# enet_phy.net
KiCad netlist of a schematic drawn in Altium Designer
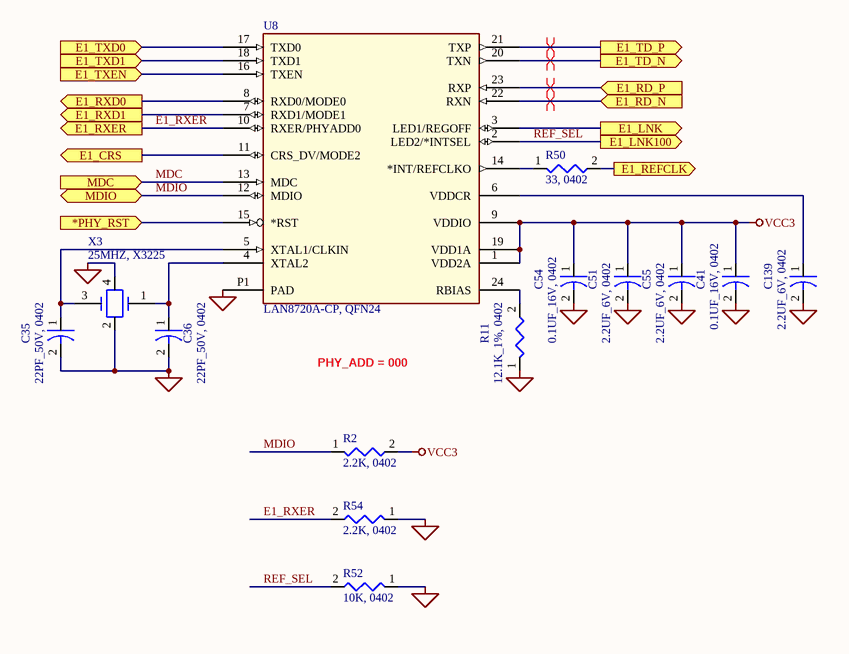
[diagram p0: enet_phy.SchDoc]

(export (version "E")
  (design (tool "Eeschema 10.0.6"))
  (components
    (comp (ref "C35")
      (value "22PF_50V, 0402")
      (footprint "0402C")
      (description "CAP - 0402 PKG")
      (libsource (lib "COGENT_Library") (part "22PF_50V, 0402"))
    )
    (comp (ref "C36")
      (value "22PF_50V, 0402")
      (footprint "0402C")
      (description "CAP - 0402 PKG")
      (libsource (lib "COGENT_Library") (part "22PF_50V, 0402"))
    )
    (comp (ref "C41")
      (value "0.1UF_16V, 0402")
      (footprint "0402C")
      (description "CAP - 0402 PKG")
      (libsource (lib "COGENT_Library") (part "0.1UF_16V, 0402"))
    )
    (comp (ref "C51")
      (value "2.2UF_6V, 0402")
      (footprint "0402C")
      (description "CAP - 0402 PKG")
      (libsource (lib "COGENT_Library") (part "2.2UF_6V, 0402"))
    )
    (comp (ref "C54")
      (value "0.1UF_16V, 0402")
      (footprint "0402C")
      (description "CAP - 0402 PKG")
      (libsource (lib "COGENT_Library") (part "0.1UF_16V, 0402"))
    )
    (comp (ref "C55")
      (value "2.2UF_6V, 0402")
      (footprint "0402C")
      (description "CAP - 0402 PKG")
      (libsource (lib "COGENT_Library") (part "2.2UF_6V, 0402"))
    )
    (comp (ref "C139")
      (value "2.2UF_6V, 0402")
      (footprint "0402C")
      (description "CAP - 0402 PKG")
      (libsource (lib "COGENT_Library") (part "2.2UF_6V, 0402"))
    )
    (comp (ref "R2")
      (value "2.2K, 0402")
      (footprint "0402R")
      (description "RES - 0402 PKG")
      (libsource (lib "COGENT_Library") (part "2.2K, 0402"))
    )
    (comp (ref "R11")
      (value "12.1K_1%, 0402")
      (footprint "0402R")
      (description "RES - 0402 PKG")
      (libsource (lib "COGENT_Library") (part "12.1K_1%, 0402"))
    )
    (comp (ref "R50")
      (value "33, 0402")
      (footprint "0402R")
      (description "RES - 0402 PKG")
      (libsource (lib "COGENT_Library") (part "33, 0402"))
    )
    (comp (ref "R52")
      (value "10K, 0402")
      (footprint "0402R")
      (description "RES - 0402 PKG")
      (libsource (lib "COGENT_Library") (part "10K, 0402"))
    )
    (comp (ref "R54")
      (value "2.2K, 0402")
      (footprint "0402R")
      (description "RES - 0402 PKG")
      (libsource (lib "COGENT_Library") (part "2.2K, 0402"))
    )
    (comp (ref "U8")
      (value "LAN8720A-CP, QFN24")
      (footprint "QFN24")
      (description "PHY - 10/100 RMII")
      (libsource (lib "COGENT_Library") (part "LAN8720A-CP, QFN24"))
    )
    (comp (ref "X3")
      (value "25MHZ, X3225")
      (footprint "X3225")
      (description "CRYSTAL - SMT, 3.2MM x 2.5MM, ABM8 PKG")
      (libsource (lib "COGENT_Library") (part "25MHZ, X3225"))
    )
  )
  (nets
    (net (code "1") (name "/*PHY_RST") (class "Default")
      (node (ref "U8") (pin "15") (pinfunction "*RST_15") (pintype "input"))
    )
    (net (code "2") (name "/E1_CRS") (class "Default")
      (node (ref "U8") (pin "11") (pinfunction "CRS_DV/MODE2_11") (pintype "bidirectional"))
    )
    (net (code "3") (name "/E1_LNK") (class "Default")
      (node (ref "U8") (pin "3") (pinfunction "LED1/REGOFF_3") (pintype "bidirectional"))
    )
    (net (code "4") (name "/E1_RD_N") (class "Default")
      (node (ref "U8") (pin "22") (pinfunction "RXN_22") (pintype "input"))
    )
    (net (code "5") (name "/E1_RD_P") (class "Default")
      (node (ref "U8") (pin "23") (pinfunction "RXP_23") (pintype "input"))
    )
    (net (code "6") (name "/E1_REFCLK") (class "Default")
      (node (ref "R50") (pin "2") (pinfunction "2_2") (pintype "passive"))
    )
    (net (code "7") (name "/E1_RXD0") (class "Default")
      (node (ref "U8") (pin "8") (pinfunction "RXD0/MODE0_8") (pintype "bidirectional"))
    )
    (net (code "8") (name "/E1_RXD1") (class "Default")
      (node (ref "U8") (pin "7") (pinfunction "RXD1/MODE1_7") (pintype "bidirectional"))
    )
    (net (code "9") (name "/E1_RXER") (class "Default")
      (node (ref "R54") (pin "2") (pinfunction "2_2") (pintype "passive"))
      (node (ref "U8") (pin "10") (pinfunction "RXER/PHYADD0_10") (pintype "bidirectional"))
    )
    (net (code "10") (name "/E1_TD_N") (class "Default")
      (node (ref "U8") (pin "20") (pinfunction "TXN_20") (pintype "output"))
    )
    (net (code "11") (name "/E1_TD_P") (class "Default")
      (node (ref "U8") (pin "21") (pinfunction "TXP_21") (pintype "output"))
    )
    (net (code "12") (name "/E1_TXD0") (class "Default")
      (node (ref "U8") (pin "17") (pinfunction "TXD0_17") (pintype "input"))
    )
    (net (code "13") (name "/E1_TXD1") (class "Default")
      (node (ref "U8") (pin "18") (pinfunction "TXD1_18") (pintype "input"))
    )
    (net (code "14") (name "/E1_TXEN") (class "Default")
      (node (ref "U8") (pin "16") (pinfunction "TXEN_16") (pintype "input"))
    )
    (net (code "15") (name "/MDC") (class "Default")
      (node (ref "U8") (pin "13") (pinfunction "MDC_13") (pintype "input"))
    )
    (net (code "16") (name "/MDIO") (class "Default")
      (node (ref "R2") (pin "1") (pinfunction "1_1") (pintype "passive"))
      (node (ref "U8") (pin "12") (pinfunction "MDIO_12") (pintype "bidirectional"))
    )
    (net (code "17") (name "/REF_SEL") (class "Default")
      (node (ref "R52") (pin "2") (pinfunction "2_2") (pintype "passive"))
      (node (ref "U8") (pin "2") (pinfunction "LED2/*INTSEL_2") (pintype "bidirectional"))
    )
    (net (code "18") (name "GND") (class "Default")
      (node (ref "C139") (pin "2") (pinfunction "2_2") (pintype "passive"))
      (node (ref "C35") (pin "2") (pinfunction "2_2") (pintype "passive"))
      (node (ref "C36") (pin "2") (pinfunction "2_2") (pintype "passive"))
      (node (ref "C41") (pin "2") (pinfunction "2_2") (pintype "passive"))
      (node (ref "C51") (pin "2") (pinfunction "2_2") (pintype "passive"))
      (node (ref "C54") (pin "2") (pinfunction "2_2") (pintype "passive"))
      (node (ref "C55") (pin "2") (pinfunction "2_2") (pintype "passive"))
      (node (ref "R11") (pin "1") (pinfunction "1_1") (pintype "passive"))
      (node (ref "R52") (pin "1") (pinfunction "1_1") (pintype "passive"))
      (node (ref "R54") (pin "1") (pinfunction "1_1") (pintype "passive"))
      (node (ref "U8") (pin "P1") (pinfunction "PAD_P1") (pintype "power_in"))
      (node (ref "X3") (pin "2") (pinfunction "2_2") (pintype "passive"))
      (node (ref "X3") (pin "4") (pinfunction "4_4") (pintype "passive"))
    )
    (net (code "19") (name "Net-(U8-*INT{slash}REFCLKO)") (class "Default")
      (node (ref "R50") (pin "1") (pinfunction "1_1") (pintype "passive"))
      (node (ref "U8") (pin "14") (pinfunction "*INT/REFCLKO_14") (pintype "output"))
    )
    (net (code "20") (name "Net-(U8-RBIAS)") (class "Default")
      (node (ref "R11") (pin "2") (pinfunction "2_2") (pintype "passive"))
      (node (ref "U8") (pin "24") (pinfunction "RBIAS_24") (pintype "passive"))
    )
    (net (code "21") (name "Net-(U8-VDDCR)") (class "Default")
      (node (ref "C139") (pin "1") (pinfunction "1_1") (pintype "passive"))
      (node (ref "U8") (pin "6") (pinfunction "VDDCR_6") (pintype "power_in"))
    )
    (net (code "22") (name "Net-(U8-XTAL1{slash}CLKIN)") (class "Default")
      (node (ref "C35") (pin "1") (pinfunction "1_1") (pintype "passive"))
      (node (ref "U8") (pin "5") (pinfunction "XTAL1/CLKIN_5") (pintype "input"))
      (node (ref "X3") (pin "3") (pinfunction "3_3") (pintype "passive"))
    )
    (net (code "23") (name "Net-(U8-XTAL2)") (class "Default")
      (node (ref "C36") (pin "1") (pinfunction "1_1") (pintype "passive"))
      (node (ref "U8") (pin "4") (pinfunction "XTAL2_4") (pintype "passive"))
      (node (ref "X3") (pin "1") (pinfunction "1_1") (pintype "passive"))
    )
    (net (code "24") (name "VCC3") (class "Default")
      (node (ref "C41") (pin "1") (pinfunction "1_1") (pintype "passive"))
      (node (ref "C51") (pin "1") (pinfunction "1_1") (pintype "passive"))
      (node (ref "C54") (pin "1") (pinfunction "1_1") (pintype "passive"))
      (node (ref "C55") (pin "1") (pinfunction "1_1") (pintype "passive"))
      (node (ref "R2") (pin "2") (pinfunction "2_2") (pintype "passive"))
      (node (ref "U8") (pin "1") (pinfunction "VDD2A_1") (pintype "power_in"))
      (node (ref "U8") (pin "19") (pinfunction "VDD1A_19") (pintype "power_in"))
      (node (ref "U8") (pin "9") (pinfunction "VDDIO_9") (pintype "power_in"))
    )
  )
)
